# 4_-RK3399_EDP_CSI_HDMI.net
KiCad netlist of a schematic drawn in Altium Designer
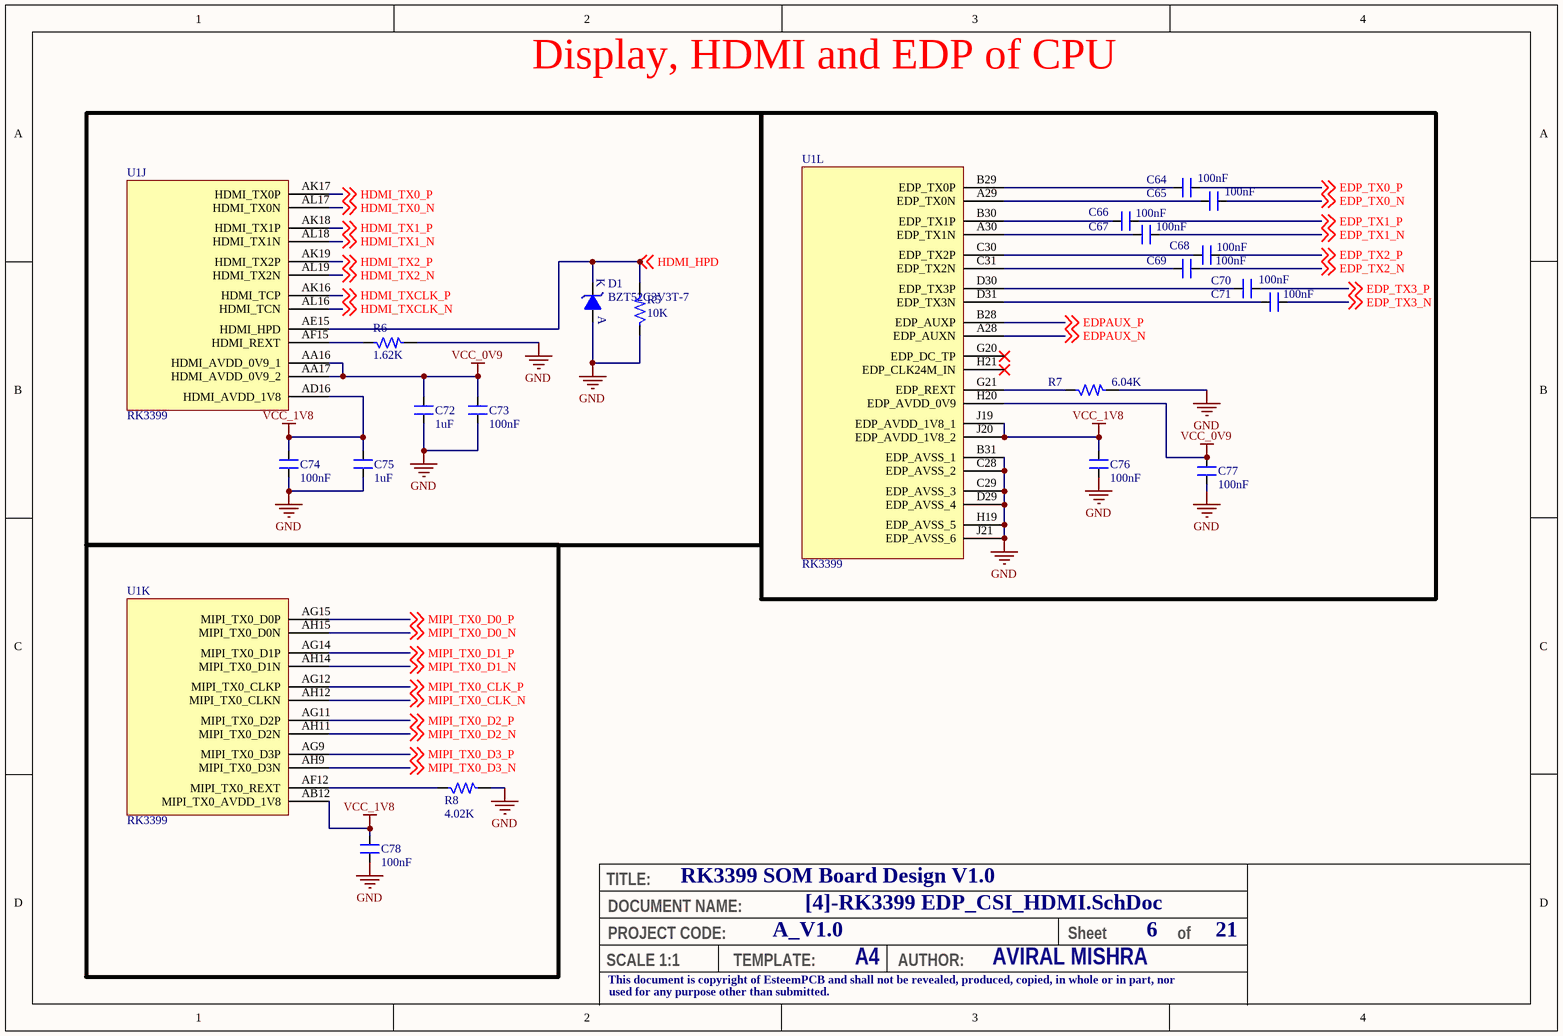
[diagram p0: [4]-RK3399 EDP_CSI_HDMI.SchDoc]

(export (version "E")
  (design (tool "Eeschema 10.0.6"))
  (components
    (comp (ref "C64")
      (value "100nF")
      (footprint "CAP_0201")
      (description "0.1µF ±10% 25V Ceramic Capacitor X5R 0201 (0603 Metric)")
      (fields
        (field (name "MANUFACTURER") "TDK Corporation")
        (field (name "MANUFACTURER PART NUMBER") "C0603X5R1E104K030BB")
      )
      (libsource (lib "RK3399 _Module_Intlib") (part "CAP_100nF-25V-10%-0201"))
    )
    (comp (ref "C65")
      (value "100nF")
      (footprint "CAP_0201")
      (description "0.1µF ±10% 25V Ceramic Capacitor X5R 0201 (0603 Metric)")
      (fields
        (field (name "MANUFACTURER") "TDK Corporation")
        (field (name "MANUFACTURER PART NUMBER") "C0603X5R1E104K030BB")
      )
      (libsource (lib "RK3399 _Module_Intlib") (part "CAP_100nF-25V-10%-0201"))
    )
    (comp (ref "C66")
      (value "100nF")
      (footprint "CAP_0201")
      (description "0.1µF ±10% 25V Ceramic Capacitor X5R 0201 (0603 Metric)")
      (fields
        (field (name "MANUFACTURER") "TDK Corporation")
        (field (name "MANUFACTURER PART NUMBER") "C0603X5R1E104K030BB")
      )
      (libsource (lib "RK3399 _Module_Intlib") (part "CAP_100nF-25V-10%-0201"))
    )
    (comp (ref "C67")
      (value "100nF")
      (footprint "CAP_0201")
      (description "0.1µF ±10% 25V Ceramic Capacitor X5R 0201 (0603 Metric)")
      (fields
        (field (name "MANUFACTURER") "TDK Corporation")
        (field (name "MANUFACTURER PART NUMBER") "C0603X5R1E104K030BB")
      )
      (libsource (lib "RK3399 _Module_Intlib") (part "CAP_100nF-25V-10%-0201"))
    )
    (comp (ref "C68")
      (value "100nF")
      (footprint "CAP_0201")
      (description "0.1µF ±10% 25V Ceramic Capacitor X5R 0201 (0603 Metric)")
      (fields
        (field (name "MANUFACTURER") "TDK Corporation")
        (field (name "MANUFACTURER PART NUMBER") "C0603X5R1E104K030BB")
      )
      (libsource (lib "RK3399 _Module_Intlib") (part "CAP_100nF-25V-10%-0201"))
    )
    (comp (ref "C69")
      (value "100nF")
      (footprint "CAP_0201")
      (description "0.1µF ±10% 25V Ceramic Capacitor X5R 0201 (0603 Metric)")
      (fields
        (field (name "MANUFACTURER") "TDK Corporation")
        (field (name "MANUFACTURER PART NUMBER") "C0603X5R1E104K030BB")
      )
      (libsource (lib "RK3399 _Module_Intlib") (part "CAP_100nF-25V-10%-0201"))
    )
    (comp (ref "C70")
      (value "100nF")
      (footprint "CAP_0201")
      (description "0.1µF ±10% 25V Ceramic Capacitor X5R 0201 (0603 Metric)")
      (fields
        (field (name "MANUFACTURER") "TDK Corporation")
        (field (name "MANUFACTURER PART NUMBER") "C0603X5R1E104K030BB")
      )
      (libsource (lib "RK3399 _Module_Intlib") (part "CAP_100nF-25V-10%-0201"))
    )
    (comp (ref "C71")
      (value "100nF")
      (footprint "CAP_0201")
      (description "0.1µF ±10% 25V Ceramic Capacitor X5R 0201 (0603 Metric)")
      (fields
        (field (name "MANUFACTURER") "TDK Corporation")
        (field (name "MANUFACTURER PART NUMBER") "C0603X5R1E104K030BB")
      )
      (libsource (lib "RK3399 _Module_Intlib") (part "CAP_100nF-25V-10%-0201"))
    )
    (comp (ref "C72")
      (value "1uF")
      (footprint "CAP_0201")
      (description "1µF ±20% 16V Ceramic Capacitor X5R 0201 (0603 Metric)")
      (fields
        (field (name "MANUFACTURER") "Samsung Electro-Mechanics")
        (field (name "MANUFACTURER PART NUMBER") "CL03A105MO3NRNH")
      )
      (libsource (lib "RK3399 _Module_Intlib") (part "CAP_1uF-16V-10%-0201"))
    )
    (comp (ref "C73")
      (value "100nF")
      (footprint "CAP_0201")
      (description "0.1µF ±10% 25V Ceramic Capacitor X5R 0201 (0603 Metric)")
      (fields
        (field (name "MANUFACTURER") "TDK Corporation")
        (field (name "MANUFACTURER PART NUMBER") "C0603X5R1E104K030BB")
      )
      (libsource (lib "RK3399 _Module_Intlib") (part "CAP_100nF-25V-10%-0201"))
    )
    (comp (ref "C74")
      (value "100nF")
      (footprint "CAP_0201")
      (description "0.1µF ±10% 25V Ceramic Capacitor X5R 0201 (0603 Metric)")
      (fields
        (field (name "MANUFACTURER") "TDK Corporation")
        (field (name "MANUFACTURER PART NUMBER") "C0603X5R1E104K030BB")
      )
      (libsource (lib "RK3399 _Module_Intlib") (part "CAP_100nF-25V-10%-0201"))
    )
    (comp (ref "C75")
      (value "1uF")
      (footprint "CAP_0201")
      (description "1µF ±20% 16V Ceramic Capacitor X5R 0201 (0603 Metric)")
      (fields
        (field (name "MANUFACTURER") "Samsung Electro-Mechanics")
        (field (name "MANUFACTURER PART NUMBER") "CL03A105MO3NRNH")
      )
      (libsource (lib "RK3399 _Module_Intlib") (part "CAP_1uF-16V-10%-0201"))
    )
    (comp (ref "C76")
      (value "100nF")
      (footprint "CAP_0201")
      (description "0.1µF ±10% 25V Ceramic Capacitor X5R 0201 (0603 Metric)")
      (fields
        (field (name "MANUFACTURER") "TDK Corporation")
        (field (name "MANUFACTURER PART NUMBER") "C0603X5R1E104K030BB")
      )
      (libsource (lib "RK3399 _Module_Intlib") (part "CAP_100nF-25V-10%-0201"))
    )
    (comp (ref "C77")
      (value "100nF")
      (footprint "CAP_0201")
      (description "0.1µF ±10% 25V Ceramic Capacitor X5R 0201 (0603 Metric)")
      (fields
        (field (name "MANUFACTURER") "TDK Corporation")
        (field (name "MANUFACTURER PART NUMBER") "C0603X5R1E104K030BB")
      )
      (libsource (lib "RK3399 _Module_Intlib") (part "CAP_100nF-25V-10%-0201"))
    )
    (comp (ref "C78")
      (value "100nF")
      (footprint "CAP_0201")
      (description "0.1µF ±10% 25V Ceramic Capacitor X5R 0201 (0603 Metric)")
      (fields
        (field (name "MANUFACTURER") "TDK Corporation")
        (field (name "MANUFACTURER PART NUMBER") "C0603X5R1E104K030BB")
      )
      (libsource (lib "RK3399 _Module_Intlib") (part "CAP_100nF-25V-10%-0201"))
    )
    (comp (ref "D1")
      (value "BZT52C3V3T-7")
      (footprint "DIO_SOD523")
      (description "Zener Diode 3.3V 300mW ±6% Surface Mount SOD-523")
      (fields (field (name "MANUFACTURER") "Diodes Incorporated"))
      (libsource (lib "RK3399 _Module_Schlib") (part "DIO-Z_3.3V-300mW-SOD-523"))
    )
    (comp (ref "R5")
      (value "10K")
      (footprint "RES_0201")
      (description "10 kOhms ±1% 0.05W, 1/20W Chip Resistor 0201 (0603 Metric) Thick Film")
      (fields
        (field (name "MANUFACTURER") "Stackpole Electronics Inc")
        (field (name "MANUFACTURER PART NUMBER") "RMCF0201FT10K0")
      )
      (libsource (lib "RK3399 _Module_Intlib") (part "RES_10K-0.05W-1%-0201"))
    )
    (comp (ref "R6")
      (value "1.62K")
      (footprint "RES_0201")
      (description "1.62 kOhms ±1% 0.05W, 1/20W Chip Resistor 0201 (0603 Metric) Automotive AEC-Q200 Thick Film")
      (fields
        (field (name "MANUFACTURER") "Panasonic Electronic Components")
        (field (name "MANUFACTURER PART NUMBER") "ERJ-1GNF1621C")
      )
      (libsource (lib "RK3399 _Module_Intlib") (part "RES_1.62K-0.05W-1%-0201"))
    )
    (comp (ref "R7")
      (value "6.04K")
      (footprint "RES_0201")
      (description "6.04 kOhms ±1% 0.05W, 1/20W Chip Resistor 0201 (0603 Metric) Thick Film")
      (fields
        (field (name "MANUFACTURER") "Panasonic Electronic Components")
        (field (name "MANUFACTURER PART NUMBER") "ERJ-1GEF6041C")
      )
      (libsource (lib "RK3399 _Module_Intlib") (part "RES_6.04K-0.05W-1%-0201"))
    )
    (comp (ref "R8")
      (value "4.02K")
      (footprint "RES_0201")
      (description "4.02 kOhms ±1% 0.05W, 1/20W Chip Resistor 0201 (0603 Metric) Thick Film")
      (fields
        (field (name "MANUFACTURER") "Yageo")
        (field (name "MANUFACTURER PART NUMBER") "RC0201FR-074K02L")
      )
      (libsource (lib "RK3399 _Module_Intlib") (part "RES_4.02K-0.05W-1%-0201"))
    )
    (comp (ref "U1")
      (value "RK3399")
      (footprint "FBGA828_23_826X826")
      (description "RK3399 is a low power, high performance processor for computing, personal mobile.")
      (fields (field (name "MANUFACTURER") "Rockchip"))
      (libsource (lib "RK3399 _Module_Schlib") (part "IC_RK3399-FCBGA828"))
    )
  )
  (nets
    (net (code "1") (name "EDPAUX_N") (class "Default")
      (node (ref "U1") (pin "A28") (pinfunction "EDP_AUXN_A28") (pintype "passive"))
    )
    (net (code "2") (name "EDPAUX_P") (class "Default")
      (node (ref "U1") (pin "B28") (pinfunction "EDP_AUXP_B28") (pintype "passive"))
    )
    (net (code "3") (name "EDP_TX0_N") (class "Default")
      (node (ref "C65") (pin "1") (pinfunction "1_1") (pintype "passive"))
    )
    (net (code "4") (name "EDP_TX0_P") (class "Default")
      (node (ref "C64") (pin "1") (pinfunction "1_1") (pintype "passive"))
    )
    (net (code "5") (name "EDP_TX1_N") (class "Default")
      (node (ref "C67") (pin "1") (pinfunction "1_1") (pintype "passive"))
    )
    (net (code "6") (name "EDP_TX1_P") (class "Default")
      (node (ref "C66") (pin "1") (pinfunction "1_1") (pintype "passive"))
    )
    (net (code "7") (name "EDP_TX2_N") (class "Default")
      (node (ref "C69") (pin "1") (pinfunction "1_1") (pintype "passive"))
    )
    (net (code "8") (name "EDP_TX2_P") (class "Default")
      (node (ref "C68") (pin "1") (pinfunction "1_1") (pintype "passive"))
    )
    (net (code "9") (name "EDP_TX3_N") (class "Default")
      (node (ref "C71") (pin "1") (pinfunction "1_1") (pintype "passive"))
    )
    (net (code "10") (name "EDP_TX3_P") (class "Default")
      (node (ref "C70") (pin "1") (pinfunction "1_1") (pintype "passive"))
    )
    (net (code "11") (name "GND") (class "Default")
      (node (ref "C72") (pin "1") (pinfunction "1_1") (pintype "passive"))
      (node (ref "C73") (pin "1") (pinfunction "1_1") (pintype "passive"))
      (node (ref "C74") (pin "1") (pinfunction "1_1") (pintype "passive"))
      (node (ref "C75") (pin "1") (pinfunction "1_1") (pintype "passive"))
      (node (ref "C76") (pin "2") (pinfunction "2_2") (pintype "passive"))
      (node (ref "C77") (pin "1") (pinfunction "1_1") (pintype "passive"))
      (node (ref "C78") (pin "1") (pinfunction "1_1") (pintype "passive"))
      (node (ref "D1") (pin "A") (pinfunction "A_A") (pintype "passive"))
      (node (ref "R5") (pin "1") (pinfunction "1_1") (pintype "passive"))
      (node (ref "R6") (pin "2") (pinfunction "2_2") (pintype "passive"))
      (node (ref "R7") (pin "2") (pinfunction "2_2") (pintype "passive"))
      (node (ref "R8") (pin "2") (pinfunction "2_2") (pintype "passive"))
      (node (ref "U1") (pin "B31") (pinfunction "EDP_AVSS_1_B31") (pintype "passive"))
      (node (ref "U1") (pin "C28") (pinfunction "EDP_AVSS_2_C28") (pintype "passive"))
      (node (ref "U1") (pin "C29") (pinfunction "EDP_AVSS_3_C29") (pintype "passive"))
      (node (ref "U1") (pin "D29") (pinfunction "EDP_AVSS_4_D29") (pintype "passive"))
      (node (ref "U1") (pin "H19") (pinfunction "EDP_AVSS_5_H19") (pintype "passive"))
      (node (ref "U1") (pin "J21") (pinfunction "EDP_AVSS_6_J21") (pintype "passive"))
    )
    (net (code "12") (name "HDMI_HPD") (class "Default")
      (node (ref "D1") (pin "K") (pinfunction "K_K") (pintype "passive"))
      (node (ref "R5") (pin "2") (pinfunction "2_2") (pintype "passive"))
      (node (ref "U1") (pin "AE15") (pinfunction "HDMI_HPD_AE15") (pintype "passive"))
    )
    (net (code "13") (name "HDMI_TX0_N") (class "Default")
      (node (ref "U1") (pin "AL17") (pinfunction "HDMI_TX0N_AL17") (pintype "passive"))
    )
    (net (code "14") (name "HDMI_TX0_P") (class "Default")
      (node (ref "U1") (pin "AK17") (pinfunction "HDMI_TX0P_AK17") (pintype "passive"))
    )
    (net (code "15") (name "HDMI_TX1_N") (class "Default")
      (node (ref "U1") (pin "AL18") (pinfunction "HDMI_TX1N_AL18") (pintype "passive"))
    )
    (net (code "16") (name "HDMI_TX1_P") (class "Default")
      (node (ref "U1") (pin "AK18") (pinfunction "HDMI_TX1P_AK18") (pintype "passive"))
    )
    (net (code "17") (name "HDMI_TX2_N") (class "Default")
      (node (ref "U1") (pin "AL19") (pinfunction "HDMI_TX2N_AL19") (pintype "passive"))
    )
    (net (code "18") (name "HDMI_TX2_P") (class "Default")
      (node (ref "U1") (pin "AK19") (pinfunction "HDMI_TX2P_AK19") (pintype "passive"))
    )
    (net (code "19") (name "HDMI_TXCLK_N") (class "Default")
      (node (ref "U1") (pin "AL16") (pinfunction "HDMI_TCN_AL16") (pintype "passive"))
    )
    (net (code "20") (name "HDMI_TXCLK_P") (class "Default")
      (node (ref "U1") (pin "AK16") (pinfunction "HDMI_TCP_AK16") (pintype "passive"))
    )
    (net (code "21") (name "MIPI_TX0_CLK_N") (class "Default")
      (node (ref "U1") (pin "AH12") (pinfunction "MIPI_TX0_CLKN_AH12") (pintype "passive"))
    )
    (net (code "22") (name "MIPI_TX0_CLK_P") (class "Default")
      (node (ref "U1") (pin "AG12") (pinfunction "MIPI_TX0_CLKP_AG12") (pintype "passive"))
    )
    (net (code "23") (name "MIPI_TX0_D0_N") (class "Default")
      (node (ref "U1") (pin "AH15") (pinfunction "MIPI_TX0_D0N_AH15") (pintype "passive"))
    )
    (net (code "24") (name "MIPI_TX0_D0_P") (class "Default")
      (node (ref "U1") (pin "AG15") (pinfunction "MIPI_TX0_D0P_AG15") (pintype "passive"))
    )
    (net (code "25") (name "MIPI_TX0_D1_N") (class "Default")
      (node (ref "U1") (pin "AH14") (pinfunction "MIPI_TX0_D1N_AH14") (pintype "passive"))
    )
    (net (code "26") (name "MIPI_TX0_D1_P") (class "Default")
      (node (ref "U1") (pin "AG14") (pinfunction "MIPI_TX0_D1P_AG14") (pintype "passive"))
    )
    (net (code "27") (name "MIPI_TX0_D2_N") (class "Default")
      (node (ref "U1") (pin "AH11") (pinfunction "MIPI_TX0_D2N_AH11") (pintype "passive"))
    )
    (net (code "28") (name "MIPI_TX0_D2_P") (class "Default")
      (node (ref "U1") (pin "AG11") (pinfunction "MIPI_TX0_D2P_AG11") (pintype "passive"))
    )
    (net (code "29") (name "MIPI_TX0_D3_N") (class "Default")
      (node (ref "U1") (pin "AH9") (pinfunction "MIPI_TX0_D3N_AH9") (pintype "passive"))
    )
    (net (code "30") (name "MIPI_TX0_D3_P") (class "Default")
      (node (ref "U1") (pin "AG9") (pinfunction "MIPI_TX0_D3P_AG9") (pintype "passive"))
    )
    (net (code "31") (name "Net-(U1J-HDMI_REXT)") (class "Default")
      (node (ref "R6") (pin "1") (pinfunction "1_1") (pintype "passive"))
      (node (ref "U1") (pin "AF15") (pinfunction "HDMI_REXT_AF15") (pintype "passive"))
    )
    (net (code "32") (name "Net-(U1K-MIPI_TX0_REXT)") (class "Default")
      (node (ref "R8") (pin "1") (pinfunction "1_1") (pintype "passive"))
      (node (ref "U1") (pin "AF12") (pinfunction "MIPI_TX0_REXT_AF12") (pintype "passive"))
    )
    (net (code "33") (name "Net-(U1L-EDP_REXT)") (class "Default")
      (node (ref "R7") (pin "1") (pinfunction "1_1") (pintype "passive"))
      (node (ref "U1") (pin "G21") (pinfunction "EDP_REXT_G21") (pintype "passive"))
    )
    (net (code "34") (name "Net-(U1L-EDP_TX0N)") (class "Default")
      (node (ref "C65") (pin "2") (pinfunction "2_2") (pintype "passive"))
      (node (ref "U1") (pin "A29") (pinfunction "EDP_TX0N_A29") (pintype "passive"))
    )
    (net (code "35") (name "Net-(U1L-EDP_TX0P)") (class "Default")
      (node (ref "C64") (pin "2") (pinfunction "2_2") (pintype "passive"))
      (node (ref "U1") (pin "B29") (pinfunction "EDP_TX0P_B29") (pintype "passive"))
    )
    (net (code "36") (name "Net-(U1L-EDP_TX1N)") (class "Default")
      (node (ref "C67") (pin "2") (pinfunction "2_2") (pintype "passive"))
      (node (ref "U1") (pin "A30") (pinfunction "EDP_TX1N_A30") (pintype "passive"))
    )
    (net (code "37") (name "Net-(U1L-EDP_TX1P)") (class "Default")
      (node (ref "C66") (pin "2") (pinfunction "2_2") (pintype "passive"))
      (node (ref "U1") (pin "B30") (pinfunction "EDP_TX1P_B30") (pintype "passive"))
    )
    (net (code "38") (name "Net-(U1L-EDP_TX2N)") (class "Default")
      (node (ref "C69") (pin "2") (pinfunction "2_2") (pintype "passive"))
      (node (ref "U1") (pin "C31") (pinfunction "EDP_TX2N_C31") (pintype "passive"))
    )
    (net (code "39") (name "Net-(U1L-EDP_TX2P)") (class "Default")
      (node (ref "C68") (pin "2") (pinfunction "2_2") (pintype "passive"))
      (node (ref "U1") (pin "C30") (pinfunction "EDP_TX2P_C30") (pintype "passive"))
    )
    (net (code "40") (name "Net-(U1L-EDP_TX3N)") (class "Default")
      (node (ref "C71") (pin "2") (pinfunction "2_2") (pintype "passive"))
      (node (ref "U1") (pin "D31") (pinfunction "EDP_TX3N_D31") (pintype "passive"))
    )
    (net (code "41") (name "Net-(U1L-EDP_TX3P)") (class "Default")
      (node (ref "C70") (pin "2") (pinfunction "2_2") (pintype "passive"))
      (node (ref "U1") (pin "D30") (pinfunction "EDP_TX3P_D30") (pintype "passive"))
    )
    (net (code "42") (name "VCC_0V9") (class "Default")
      (node (ref "C72") (pin "2") (pinfunction "2_2") (pintype "passive"))
      (node (ref "C73") (pin "2") (pinfunction "2_2") (pintype "passive"))
      (node (ref "C77") (pin "2") (pinfunction "2_2") (pintype "passive"))
      (node (ref "U1") (pin "AA16") (pinfunction "HDMI_AVDD_0V9_1_AA16") (pintype "passive"))
      (node (ref "U1") (pin "AA17") (pinfunction "HDMI_AVDD_0V9_2_AA17") (pintype "passive"))
      (node (ref "U1") (pin "H20") (pinfunction "EDP_AVDD_0V9_H20") (pintype "passive"))
    )
    (net (code "43") (name "VCC_1V8") (class "Default")
      (node (ref "C74") (pin "2") (pinfunction "2_2") (pintype "passive"))
      (node (ref "C75") (pin "2") (pinfunction "2_2") (pintype "passive"))
      (node (ref "C76") (pin "1") (pinfunction "1_1") (pintype "passive"))
      (node (ref "C78") (pin "2") (pinfunction "2_2") (pintype "passive"))
      (node (ref "U1") (pin "AB12") (pinfunction "MIPI_TX0_AVDD_1V8_AB12") (pintype "passive"))
      (node (ref "U1") (pin "AD16") (pinfunction "HDMI_AVDD_1V8_AD16") (pintype "passive"))
      (node (ref "U1") (pin "J19") (pinfunction "EDP_AVDD_1V8_1_J19") (pintype "passive"))
      (node (ref "U1") (pin "J20") (pinfunction "EDP_AVDD_1V8_2_J20") (pintype "passive"))
    )
    (net (code "44") (name "unconnected-(U1L-EDP_CLK24M_IN-PadH21)") (class "Default")
      (node (ref "U1") (pin "H21") (pinfunction "EDP_CLK24M_IN_H21") (pintype "passive+no_connect"))
    )
    (net (code "45") (name "unconnected-(U1L-EDP_DC_TP-PadG20)") (class "Default")
      (node (ref "U1") (pin "G20") (pinfunction "EDP_DC_TP_G20") (pintype "passive+no_connect"))
    )
  )
)
